# slave.net
KiCad netlist of a schematic drawn in Altium Designer
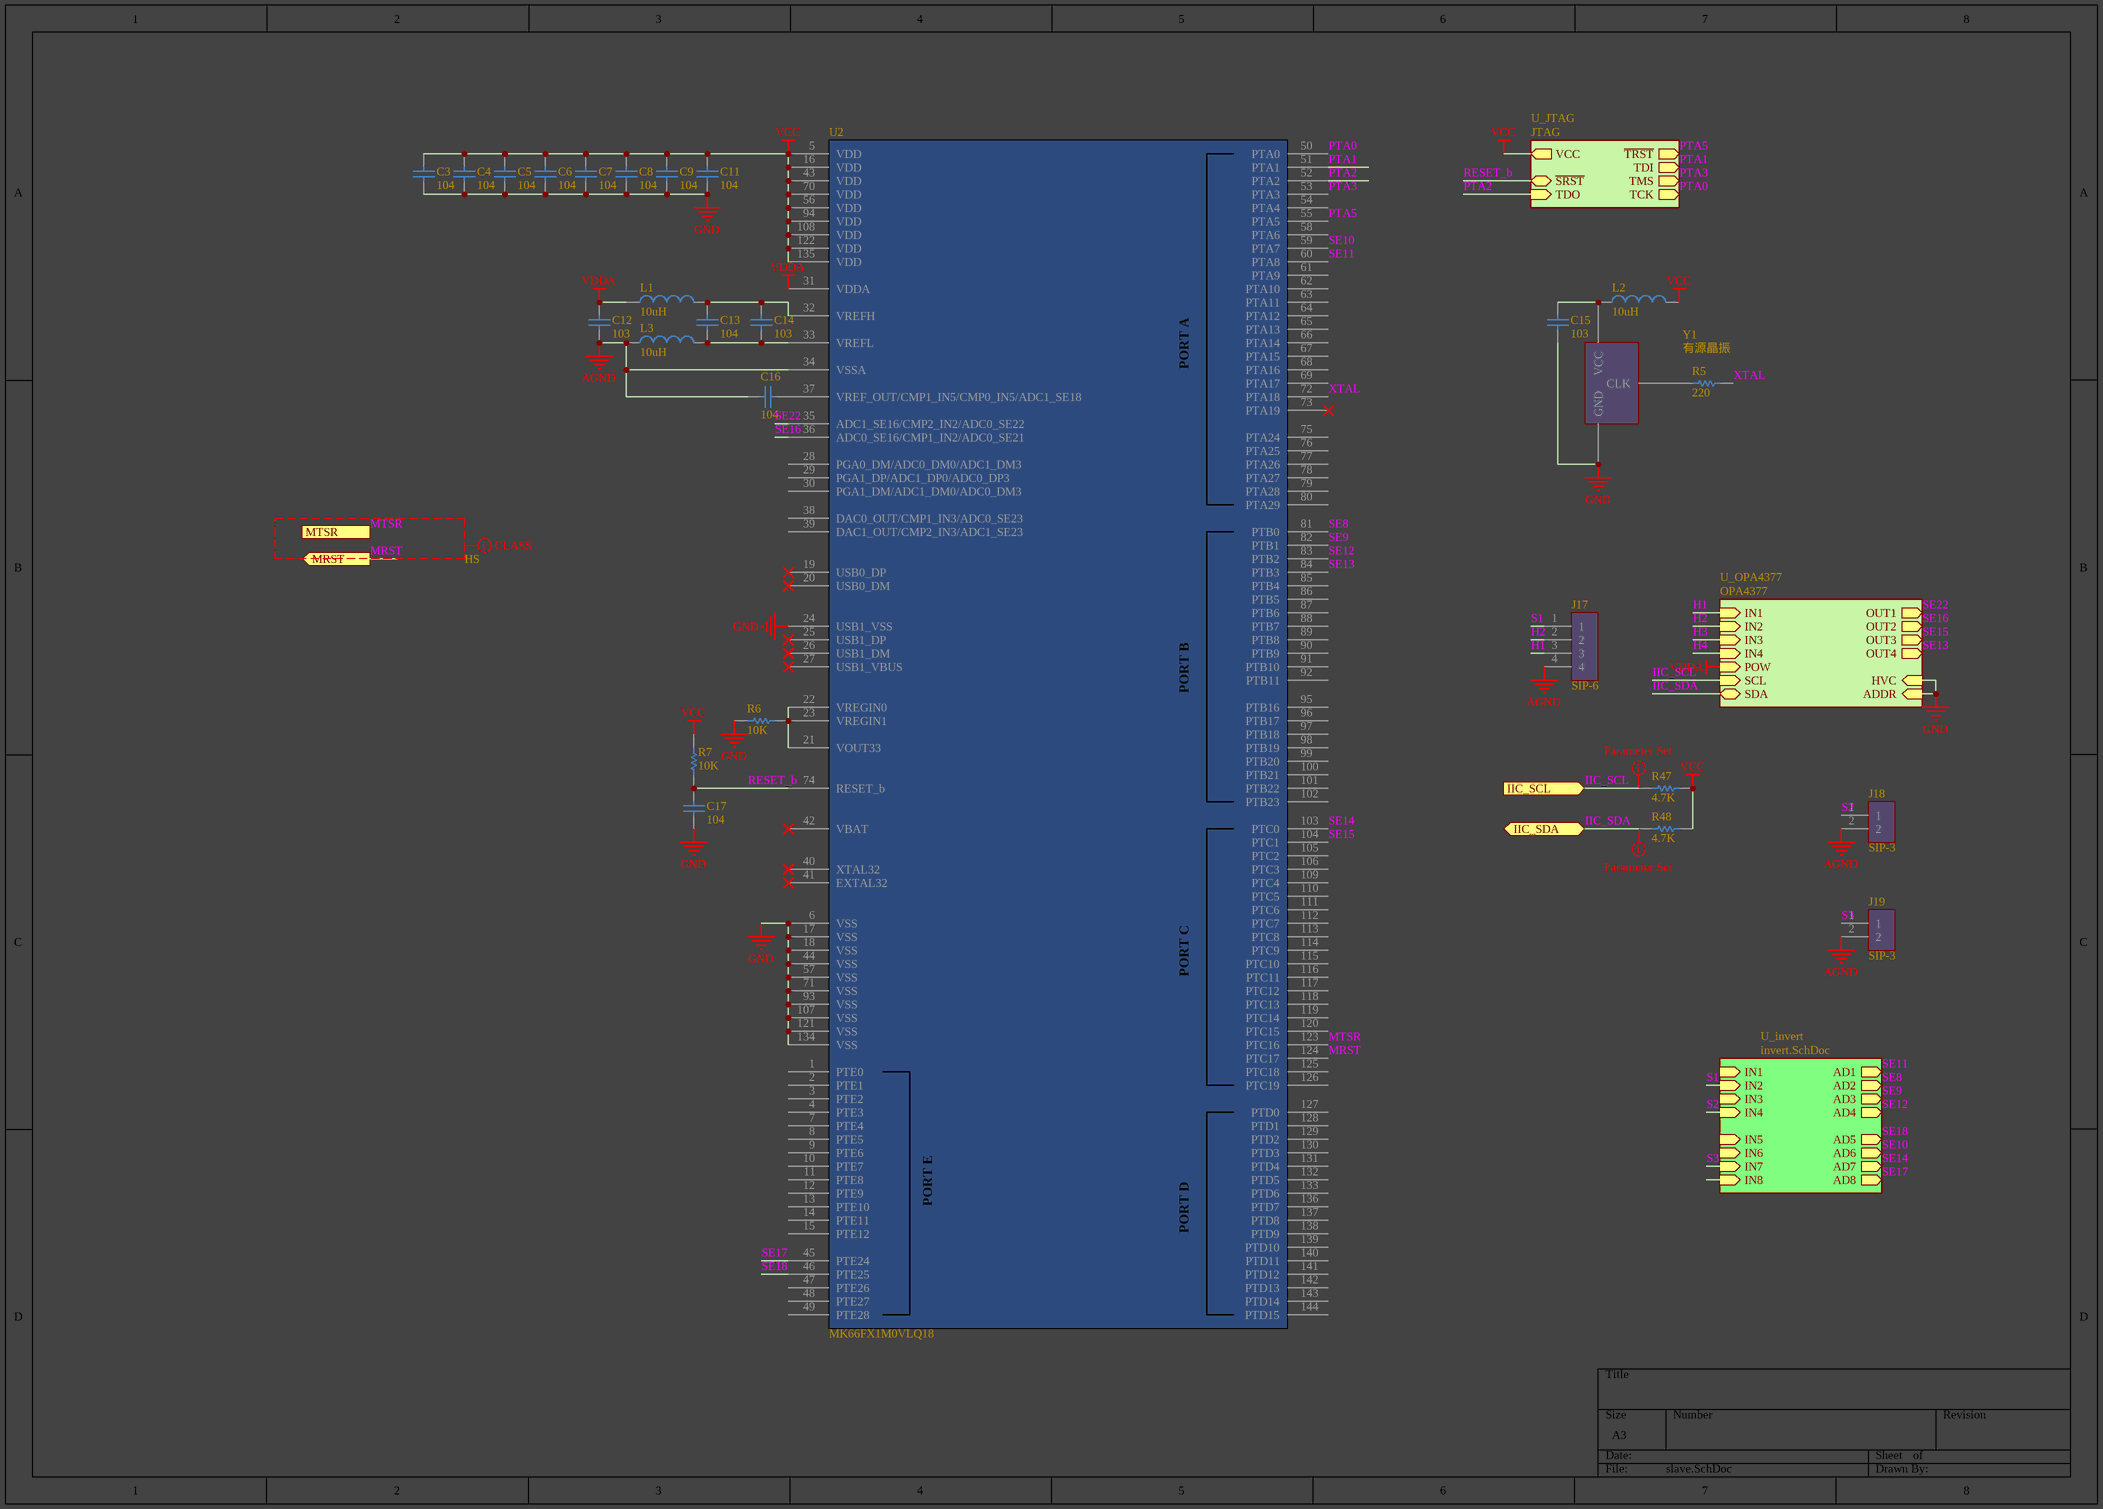
[diagram p0: slave.SchDoc]

(export (version "E")
  (design (tool "Eeschema 10.0.6"))
  (components
    (comp (ref "C3")
      (value "104")
      (footprint "C0603")
      (description "Capacitor")
      (fields (field (name "PUBLISHER") "Altium Limited"))
      (libsource (lib "iMag") (part "电容"))
    )
    (comp (ref "C4")
      (value "104")
      (footprint "C0603")
      (description "Capacitor")
      (fields (field (name "PUBLISHER") "Altium Limited"))
      (libsource (lib "iMag") (part "电容"))
    )
    (comp (ref "C5")
      (value "104")
      (footprint "C0603")
      (description "Capacitor")
      (fields (field (name "PUBLISHER") "Altium Limited"))
      (libsource (lib "iMag") (part "电容"))
    )
    (comp (ref "C6")
      (value "104")
      (footprint "C0603")
      (description "Capacitor")
      (fields (field (name "PUBLISHER") "Altium Limited"))
      (libsource (lib "iMag") (part "电容"))
    )
    (comp (ref "C7")
      (value "104")
      (footprint "C0603")
      (description "Capacitor")
      (fields (field (name "PUBLISHER") "Altium Limited"))
      (libsource (lib "iMag") (part "电容"))
    )
    (comp (ref "C8")
      (value "104")
      (footprint "C0603")
      (description "Capacitor")
      (fields (field (name "PUBLISHER") "Altium Limited"))
      (libsource (lib "iMag") (part "电容"))
    )
    (comp (ref "C9")
      (value "104")
      (footprint "C0603")
      (description "Capacitor")
      (fields (field (name "PUBLISHER") "Altium Limited"))
      (libsource (lib "iMag") (part "电容"))
    )
    (comp (ref "C11")
      (value "104")
      (footprint "C0603")
      (description "Capacitor")
      (fields (field (name "PUBLISHER") "Altium Limited"))
      (libsource (lib "iMag") (part "电容"))
    )
    (comp (ref "C12")
      (value "103")
      (footprint "C0603")
      (description "Capacitor")
      (fields (field (name "PUBLISHER") "Altium Limited"))
      (libsource (lib "iMag") (part "电容"))
    )
    (comp (ref "C13")
      (value "104")
      (footprint "C0603")
      (description "Capacitor")
      (fields (field (name "PUBLISHER") "Altium Limited"))
      (libsource (lib "iMag") (part "电容"))
    )
    (comp (ref "C14")
      (value "103")
      (footprint "C0603")
      (description "Capacitor")
      (fields (field (name "PUBLISHER") "Altium Limited"))
      (libsource (lib "iMag") (part "电容"))
    )
    (comp (ref "C15")
      (value "103")
      (footprint "C0603")
      (description "Capacitor")
      (fields (field (name "PUBLISHER") "Altium Limited"))
      (libsource (lib "iMag") (part "电容"))
    )
    (comp (ref "C16")
      (value "104")
      (footprint "C0402")
      (description "Capacitor")
      (fields (field (name "PUBLISHER") "Altium Limited"))
      (libsource (lib "iMag") (part "电容"))
    )
    (comp (ref "C17")
      (value "104")
      (footprint "C0603")
      (description "Capacitor")
      (fields (field (name "PUBLISHER") "Altium Limited"))
      (libsource (lib "iMag") (part "电容"))
    )
    (comp (ref "J17") (value "SIP-6") (footprint "2.0排针4P") (libsource (lib "iMag") (part "SIP-4")))
    (comp (ref "J18") (value "SIP-3") (footprint "GH1.25-2P") (libsource (lib "iMag") (part "SIP-2")))
    (comp (ref "J19") (value "SIP-3") (footprint "GH1.25-2P") (libsource (lib "iMag") (part "SIP-2")))
    (comp (ref "L1") (value "10uH") (footprint "L0603") (libsource (lib "iMag") (part "电感")))
    (comp (ref "L2") (value "10uH") (footprint "L0603") (libsource (lib "iMag") (part "电感")))
    (comp (ref "L3") (value "10uH") (footprint "L0603") (libsource (lib "iMag") (part "电感")))
    (comp (ref "R5")
      (value "220")
      (footprint "R0402")
      (description "Resistor")
      (fields (field (name "PUBLISHER") "Altium Limited"))
      (libsource (lib "iMag") (part "电阻"))
    )
    (comp (ref "R6")
      (value "10K")
      (footprint "R0603")
      (description "Resistor")
      (fields (field (name "PUBLISHER") "Altium Limited"))
      (libsource (lib "iMag") (part "电阻"))
    )
    (comp (ref "R7")
      (value "10K")
      (footprint "R0603")
      (description "Resistor")
      (fields (field (name "PUBLISHER") "Altium Limited"))
      (libsource (lib "iMag") (part "电阻"))
    )
    (comp (ref "R47")
      (value "4.7K")
      (footprint "R0603")
      (description "Resistor")
      (fields (field (name "PUBLISHER") "Altium Limited"))
      (libsource (lib "iMag") (part "电阻"))
    )
    (comp (ref "R48")
      (value "4.7K")
      (footprint "R0603")
      (description "Resistor")
      (fields (field (name "PUBLISHER") "Altium Limited"))
      (libsource (lib "iMag") (part "电阻"))
    )
    (comp (ref "U2")
      (value "MK66FX1M0VLQ18")
      (footprint "LQFP144 20X20")
      (libsource (lib "iMag") (part "MK66"))
    )
    (comp (ref "Y1") (value "有源晶振") (footprint "OSC 5032-4P") (libsource (lib "iMag") (part "有源晶振")))
  )
  (nets
    (net (code "1") (name "/H1") (class "Default")
      (node (ref "J17") (pin "3") (pinfunction "3_3") (pintype "passive"))
    )
    (net (code "2") (name "/H2") (class "Default")
      (node (ref "J17") (pin "2") (pinfunction "2_2") (pintype "passive"))
    )
    (net (code "5") (name "/IIC_SCL") (class "Default")
      (node (ref "R47") (pin "2") (pinfunction "2_2") (pintype "passive"))
    )
    (net (code "6") (name "/IIC_SDA") (class "Default")
      (node (ref "R48") (pin "2") (pinfunction "2_2") (pintype "passive"))
    )
    (net (code "12") (name "/MRST") (class "Default")
      (node (ref "U2") (pin "124") (pinfunction "PTC17_124") (pintype "passive"))
    )
    (net (code "13") (name "/MTSR") (class "Default")
      (node (ref "U2") (pin "123") (pinfunction "PTC16_123") (pintype "passive"))
    )
    (net (code "14") (name "/PTA0") (class "Default")
      (node (ref "U2") (pin "50") (pinfunction "PTA0_50") (pintype "passive"))
    )
    (net (code "15") (name "/PTA1") (class "Default")
      (node (ref "U2") (pin "51") (pinfunction "PTA1_51") (pintype "passive"))
    )
    (net (code "16") (name "/PTA2") (class "Default")
      (node (ref "U2") (pin "52") (pinfunction "PTA2_52") (pintype "passive"))
    )
    (net (code "17") (name "/PTA3") (class "Default")
      (node (ref "U2") (pin "53") (pinfunction "PTA3_53") (pintype "passive"))
    )
    (net (code "18") (name "/PTA5") (class "Default")
      (node (ref "U2") (pin "55") (pinfunction "PTA5_55") (pintype "passive"))
    )
    (net (code "19") (name "/RESET_b") (class "Default")
      (node (ref "C17") (pin "2") (pinfunction "2_2") (pintype "passive"))
      (node (ref "R7") (pin "1") (pinfunction "1_1") (pintype "passive"))
      (node (ref "U2") (pin "74") (pinfunction "RESET_b_74") (pintype "passive"))
    )
    (net (code "20") (name "/S1") (class "Default")
      (node (ref "J17") (pin "1") (pinfunction "1_1") (pintype "passive"))
    )
    (net (code "21") (name "/S2") (class "Default")
      (node (ref "J18") (pin "1") (pinfunction "1_1") (pintype "passive"))
    )
    (net (code "22") (name "/S3") (class "Default")
      (node (ref "J19") (pin "1") (pinfunction "1_1") (pintype "passive"))
    )
    (net (code "23") (name "/SE8") (class "Default")
      (node (ref "U2") (pin "81") (pinfunction "PTB0_81") (pintype "passive"))
    )
    (net (code "24") (name "/SE9") (class "Default")
      (node (ref "U2") (pin "82") (pinfunction "PTB1_82") (pintype "passive"))
    )
    (net (code "25") (name "/SE10") (class "Default")
      (node (ref "U2") (pin "59") (pinfunction "PTA7_59") (pintype "passive"))
    )
    (net (code "26") (name "/SE11") (class "Default")
      (node (ref "U2") (pin "60") (pinfunction "PTA8_60") (pintype "passive"))
    )
    (net (code "27") (name "/SE12") (class "Default")
      (node (ref "U2") (pin "83") (pinfunction "PTB2_83") (pintype "passive"))
    )
    (net (code "28") (name "/SE13") (class "Default")
      (node (ref "U2") (pin "84") (pinfunction "PTB3_84") (pintype "passive"))
    )
    (net (code "29") (name "/SE14") (class "Default")
      (node (ref "U2") (pin "103") (pinfunction "PTC0_103") (pintype "passive"))
    )
    (net (code "30") (name "/SE15") (class "Default")
      (node (ref "U2") (pin "104") (pinfunction "PTC1_104") (pintype "passive"))
    )
    (net (code "31") (name "/SE16") (class "Default")
      (node (ref "U2") (pin "36") (pinfunction "ADC0_SE16/CMP1_IN2/ADC0_SE21_36") (pintype "passive"))
    )
    (net (code "32") (name "/SE17") (class "Default")
      (node (ref "U2") (pin "45") (pinfunction "PTE24_45") (pintype "passive"))
    )
    (net (code "33") (name "/SE18") (class "Default")
      (node (ref "U2") (pin "46") (pinfunction "PTE25_46") (pintype "passive"))
    )
    (net (code "34") (name "/SE22") (class "Default")
      (node (ref "U2") (pin "35") (pinfunction "ADC1_SE16/CMP2_IN2/ADC0_SE22_35") (pintype "passive"))
    )
    (net (code "35") (name "/XTAL") (class "Default")
      (node (ref "R5") (pin "1") (pinfunction "1_1") (pintype "passive"))
      (node (ref "U2") (pin "72") (pinfunction "PTA18_72") (pintype "passive"))
    )
    (net (code "36") (name "AGND") (class "Default")
      (node (ref "C12") (pin "1") (pinfunction "1_1") (pintype "passive"))
      (node (ref "C16") (pin "1") (pinfunction "1_1") (pintype "passive"))
      (node (ref "J17") (pin "4") (pinfunction "4_4") (pintype "passive"))
      (node (ref "J18") (pin "2") (pinfunction "2_2") (pintype "passive"))
      (node (ref "J19") (pin "2") (pinfunction "2_2") (pintype "passive"))
      (node (ref "L3") (pin "1") (pinfunction "1_1") (pintype "passive"))
      (node (ref "U2") (pin "34") (pinfunction "VSSA_34") (pintype "passive"))
    )
    (net (code "37") (name "GND") (class "Default")
      (node (ref "C11") (pin "1") (pinfunction "1_1") (pintype "passive"))
      (node (ref "C15") (pin "1") (pinfunction "1_1") (pintype "passive"))
      (node (ref "C17") (pin "1") (pinfunction "1_1") (pintype "passive"))
      (node (ref "C3") (pin "1") (pinfunction "1_1") (pintype "passive"))
      (node (ref "C4") (pin "1") (pinfunction "1_1") (pintype "passive"))
      (node (ref "C5") (pin "1") (pinfunction "1_1") (pintype "passive"))
      (node (ref "C6") (pin "1") (pinfunction "1_1") (pintype "passive"))
      (node (ref "C7") (pin "1") (pinfunction "1_1") (pintype "passive"))
      (node (ref "C8") (pin "1") (pinfunction "1_1") (pintype "passive"))
      (node (ref "C9") (pin "1") (pinfunction "1_1") (pintype "passive"))
      (node (ref "R6") (pin "2") (pinfunction "2_2") (pintype "passive"))
      (node (ref "U2") (pin "107") (pinfunction "VSS_107") (pintype "passive"))
      (node (ref "U2") (pin "121") (pinfunction "VSS_121") (pintype "passive"))
      (node (ref "U2") (pin "134") (pinfunction "VSS_134") (pintype "passive"))
      (node (ref "U2") (pin "17") (pinfunction "VSS_17") (pintype "passive"))
      (node (ref "U2") (pin "18") (pinfunction "VSS_18") (pintype "passive"))
      (node (ref "U2") (pin "24") (pinfunction "USB1_VSS_24") (pintype "passive"))
      (node (ref "U2") (pin "44") (pinfunction "VSS_44") (pintype "passive"))
      (node (ref "U2") (pin "57") (pinfunction "VSS_57") (pintype "passive"))
      (node (ref "U2") (pin "6") (pinfunction "VSS_6") (pintype "passive"))
      (node (ref "U2") (pin "71") (pinfunction "VSS_71") (pintype "passive"))
      (node (ref "U2") (pin "93") (pinfunction "VSS_93") (pintype "passive"))
      (node (ref "Y1") (pin "2") (pinfunction "GND_2") (pintype "passive"))
    )
    (net (code "38") (name "Net-(U2-VOUT33)") (class "Default")
      (node (ref "R6") (pin "1") (pinfunction "1_1") (pintype "passive"))
      (node (ref "U2") (pin "21") (pinfunction "VOUT33_21") (pintype "passive"))
      (node (ref "U2") (pin "22") (pinfunction "VREGIN0_22") (pintype "passive"))
      (node (ref "U2") (pin "23") (pinfunction "VREGIN1_23") (pintype "passive"))
    )
    (net (code "39") (name "Net-(U2-VREFH)") (class "Default")
      (node (ref "C13") (pin "2") (pinfunction "2_2") (pintype "passive"))
      (node (ref "C14") (pin "2") (pinfunction "2_2") (pintype "passive"))
      (node (ref "L1") (pin "2") (pinfunction "2_2") (pintype "passive"))
      (node (ref "U2") (pin "32") (pinfunction "VREFH_32") (pintype "passive"))
    )
    (net (code "40") (name "Net-(U2-VREFL)") (class "Default")
      (node (ref "C13") (pin "1") (pinfunction "1_1") (pintype "passive"))
      (node (ref "C14") (pin "1") (pinfunction "1_1") (pintype "passive"))
      (node (ref "L3") (pin "2") (pinfunction "2_2") (pintype "passive"))
      (node (ref "U2") (pin "33") (pinfunction "VREFL_33") (pintype "passive"))
    )
    (net (code "41") (name "Net-(U2-VREF_OUT{slash}CMP1_IN5{slash}CMP0_IN5{slash}ADC1_SE18)") (class "Default")
      (node (ref "C16") (pin "2") (pinfunction "2_2") (pintype "passive"))
      (node (ref "U2") (pin "37") (pinfunction "VREF_OUT/CMP1_IN5/CMP0_IN5/ADC1_SE18_37") (pintype "passive"))
    )
    (net (code "42") (name "Net-(Y1-CLK)") (class "Default")
      (node (ref "R5") (pin "2") (pinfunction "2_2") (pintype "passive"))
      (node (ref "Y1") (pin "3") (pinfunction "CLK_3") (pintype "passive"))
    )
    (net (code "43") (name "Net-(Y1-VCC)") (class "Default")
      (node (ref "C15") (pin "2") (pinfunction "2_2") (pintype "passive"))
      (node (ref "L2") (pin "1") (pinfunction "1_1") (pintype "passive"))
      (node (ref "Y1") (pin "4") (pinfunction "VCC_4") (pintype "passive"))
    )
    (net (code "44") (name "VCC") (class "Default")
      (node (ref "C11") (pin "2") (pinfunction "2_2") (pintype "passive"))
      (node (ref "C3") (pin "2") (pinfunction "2_2") (pintype "passive"))
      (node (ref "C4") (pin "2") (pinfunction "2_2") (pintype "passive"))
      (node (ref "C5") (pin "2") (pinfunction "2_2") (pintype "passive"))
      (node (ref "C6") (pin "2") (pinfunction "2_2") (pintype "passive"))
      (node (ref "C7") (pin "2") (pinfunction "2_2") (pintype "passive"))
      (node (ref "C8") (pin "2") (pinfunction "2_2") (pintype "passive"))
      (node (ref "C9") (pin "2") (pinfunction "2_2") (pintype "passive"))
      (node (ref "L2") (pin "2") (pinfunction "2_2") (pintype "passive"))
      (node (ref "R47") (pin "1") (pinfunction "1_1") (pintype "passive"))
      (node (ref "R48") (pin "1") (pinfunction "1_1") (pintype "passive"))
      (node (ref "R7") (pin "2") (pinfunction "2_2") (pintype "passive"))
      (node (ref "U2") (pin "108") (pinfunction "VDD_108") (pintype "passive"))
      (node (ref "U2") (pin "122") (pinfunction "VDD_122") (pintype "passive"))
      (node (ref "U2") (pin "135") (pinfunction "VDD_135") (pintype "passive"))
      (node (ref "U2") (pin "16") (pinfunction "VDD_16") (pintype "passive"))
      (node (ref "U2") (pin "43") (pinfunction "VDD_43") (pintype "passive"))
      (node (ref "U2") (pin "5") (pinfunction "VDD_5") (pintype "passive"))
      (node (ref "U2") (pin "56") (pinfunction "VDD_56") (pintype "passive"))
      (node (ref "U2") (pin "70") (pinfunction "VDD_70") (pintype "passive"))
      (node (ref "U2") (pin "94") (pinfunction "VDD_94") (pintype "passive"))
    )
    (net (code "45") (name "VDDA") (class "Default")
      (node (ref "C12") (pin "2") (pinfunction "2_2") (pintype "passive"))
      (node (ref "L1") (pin "1") (pinfunction "1_1") (pintype "passive"))
      (node (ref "U2") (pin "31") (pinfunction "VDDA_31") (pintype "passive"))
    )
    (net (code "46") (name "unconnected-(U2-DAC0_OUT{slash}CMP1_IN3{slash}ADC0_SE23-Pad38)") (class "Default")
      (node (ref "U2") (pin "38") (pinfunction "DAC0_OUT/CMP1_IN3/ADC0_SE23_38") (pintype "passive"))
    )
    (net (code "47") (name "unconnected-(U2-DAC1_OUT{slash}CMP2_IN3{slash}ADC1_SE23-Pad39)") (class "Default")
      (node (ref "U2") (pin "39") (pinfunction "DAC1_OUT/CMP2_IN3/ADC1_SE23_39") (pintype "passive"))
    )
    (net (code "48") (name "unconnected-(U2-EXTAL32-Pad41)") (class "Default")
      (node (ref "U2") (pin "41") (pinfunction "EXTAL32_41") (pintype "passive+no_connect"))
    )
    (net (code "49") (name "unconnected-(U2-PGA0_DM{slash}ADC0_DM0{slash}ADC1_DM3-Pad28)") (class "Default")
      (node (ref "U2") (pin "28") (pinfunction "PGA0_DM/ADC0_DM0/ADC1_DM3_28") (pintype "passive"))
    )
    (net (code "50") (name "unconnected-(U2-PGA1_DM{slash}ADC1_DM0{slash}ADC0_DM3-Pad30)") (class "Default")
      (node (ref "U2") (pin "30") (pinfunction "PGA1_DM/ADC1_DM0/ADC0_DM3_30") (pintype "passive"))
    )
    (net (code "51") (name "unconnected-(U2-PGA1_DP{slash}ADC1_DP0{slash}ADC0_DP3-Pad29)") (class "Default")
      (node (ref "U2") (pin "29") (pinfunction "PGA1_DP/ADC1_DP0/ADC0_DP3_29") (pintype "passive"))
    )
    (net (code "52") (name "unconnected-(U2-PTA4-Pad54)") (class "Default")
      (node (ref "U2") (pin "54") (pinfunction "PTA4_54") (pintype "passive"))
    )
    (net (code "53") (name "unconnected-(U2-PTA6-Pad58)") (class "Default")
      (node (ref "U2") (pin "58") (pinfunction "PTA6_58") (pintype "passive"))
    )
    (net (code "54") (name "unconnected-(U2-PTA9-Pad61)") (class "Default")
      (node (ref "U2") (pin "61") (pinfunction "PTA9_61") (pintype "passive"))
    )
    (net (code "55") (name "unconnected-(U2-PTA10-Pad62)") (class "Default")
      (node (ref "U2") (pin "62") (pinfunction "PTA10_62") (pintype "passive"))
    )
    (net (code "56") (name "unconnected-(U2-PTA11-Pad63)") (class "Default")
      (node (ref "U2") (pin "63") (pinfunction "PTA11_63") (pintype "passive"))
    )
    (net (code "57") (name "unconnected-(U2-PTA12-Pad64)") (class "Default")
      (node (ref "U2") (pin "64") (pinfunction "PTA12_64") (pintype "passive"))
    )
    (net (code "58") (name "unconnected-(U2-PTA13-Pad65)") (class "Default")
      (node (ref "U2") (pin "65") (pinfunction "PTA13_65") (pintype "passive"))
    )
    (net (code "59") (name "unconnected-(U2-PTA14-Pad66)") (class "Default")
      (node (ref "U2") (pin "66") (pinfunction "PTA14_66") (pintype "passive"))
    )
    (net (code "60") (name "unconnected-(U2-PTA15-Pad67)") (class "Default")
      (node (ref "U2") (pin "67") (pinfunction "PTA15_67") (pintype "passive"))
    )
    (net (code "61") (name "unconnected-(U2-PTA16-Pad68)") (class "Default")
      (node (ref "U2") (pin "68") (pinfunction "PTA16_68") (pintype "passive"))
    )
    (net (code "62") (name "unconnected-(U2-PTA17-Pad69)") (class "Default")
      (node (ref "U2") (pin "69") (pinfunction "PTA17_69") (pintype "passive"))
    )
    (net (code "63") (name "unconnected-(U2-PTA19-Pad73)") (class "Default")
      (node (ref "U2") (pin "73") (pinfunction "PTA19_73") (pintype "passive+no_connect"))
    )
    (net (code "64") (name "unconnected-(U2-PTA24-Pad75)") (class "Default")
      (node (ref "U2") (pin "75") (pinfunction "PTA24_75") (pintype "passive"))
    )
    (net (code "65") (name "unconnected-(U2-PTA25-Pad76)") (class "Default")
      (node (ref "U2") (pin "76") (pinfunction "PTA25_76") (pintype "passive"))
    )
    (net (code "66") (name "unconnected-(U2-PTA26-Pad77)") (class "Default")
      (node (ref "U2") (pin "77") (pinfunction "PTA26_77") (pintype "passive"))
    )
    (net (code "67") (name "unconnected-(U2-PTA27-Pad78)") (class "Default")
      (node (ref "U2") (pin "78") (pinfunction "PTA27_78") (pintype "passive"))
    )
    (net (code "68") (name "unconnected-(U2-PTA28-Pad79)") (class "Default")
      (node (ref "U2") (pin "79") (pinfunction "PTA28_79") (pintype "passive"))
    )
    (net (code "69") (name "unconnected-(U2-PTA29-Pad80)") (class "Default")
      (node (ref "U2") (pin "80") (pinfunction "PTA29_80") (pintype "passive"))
    )
    (net (code "70") (name "unconnected-(U2-PTB4-Pad85)") (class "Default")
      (node (ref "U2") (pin "85") (pinfunction "PTB4_85") (pintype "passive"))
    )
    (net (code "71") (name "unconnected-(U2-PTB5-Pad86)") (class "Default")
      (node (ref "U2") (pin "86") (pinfunction "PTB5_86") (pintype "passive"))
    )
    (net (code "72") (name "unconnected-(U2-PTB6-Pad87)") (class "Default")
      (node (ref "U2") (pin "87") (pinfunction "PTB6_87") (pintype "passive"))
    )
    (net (code "73") (name "unconnected-(U2-PTB7-Pad88)") (class "Default")
      (node (ref "U2") (pin "88") (pinfunction "PTB7_88") (pintype "passive"))
    )
    (net (code "74") (name "unconnected-(U2-PTB8-Pad89)") (class "Default")
      (node (ref "U2") (pin "89") (pinfunction "PTB8_89") (pintype "passive"))
    )
    (net (code "75") (name "unconnected-(U2-PTB9-Pad90)") (class "Default")
      (node (ref "U2") (pin "90") (pinfunction "PTB9_90") (pintype "passive"))
    )
    (net (code "76") (name "unconnected-(U2-PTB10-Pad91)") (class "Default")
      (node (ref "U2") (pin "91") (pinfunction "PTB10_91") (pintype "passive"))
    )
    (net (code "77") (name "unconnected-(U2-PTB11-Pad92)") (class "Default")
      (node (ref "U2") (pin "92") (pinfunction "PTB11_92") (pintype "passive"))
    )
    (net (code "78") (name "unconnected-(U2-PTB16-Pad95)") (class "Default")
      (node (ref "U2") (pin "95") (pinfunction "PTB16_95") (pintype "passive"))
    )
    (net (code "79") (name "unconnected-(U2-PTB17-Pad96)") (class "Default")
      (node (ref "U2") (pin "96") (pinfunction "PTB17_96") (pintype "passive"))
    )
    (net (code "80") (name "unconnected-(U2-PTB18-Pad97)") (class "Default")
      (node (ref "U2") (pin "97") (pinfunction "PTB18_97") (pintype "passive"))
    )
    (net (code "81") (name "unconnected-(U2-PTB19-Pad98)") (class "Default")
      (node (ref "U2") (pin "98") (pinfunction "PTB19_98") (pintype "passive"))
    )
    (net (code "82") (name "unconnected-(U2-PTB20-Pad99)") (class "Default")
      (node (ref "U2") (pin "99") (pinfunction "PTB20_99") (pintype "passive"))
    )
    (net (code "83") (name "unconnected-(U2-PTB21-Pad100)") (class "Default")
      (node (ref "U2") (pin "100") (pinfunction "PTB21_100") (pintype "passive"))
    )
    (net (code "84") (name "unconnected-(U2-PTB22-Pad101)") (class "Default")
      (node (ref "U2") (pin "101") (pinfunction "PTB22_101") (pintype "passive"))
    )
    (net (code "85") (name "unconnected-(U2-PTB23-Pad102)") (class "Default")
      (node (ref "U2") (pin "102") (pinfunction "PTB23_102") (pintype "passive"))
    )
    (net (code "86") (name "unconnected-(U2-PTC2-Pad105)") (class "Default")
      (node (ref "U2") (pin "105") (pinfunction "PTC2_105") (pintype "passive"))
    )
    (net (code "87") (name "unconnected-(U2-PTC3-Pad106)") (class "Default")
      (node (ref "U2") (pin "106") (pinfunction "PTC3_106") (pintype "passive"))
    )
    (net (code "88") (name "unconnected-(U2-PTC4-Pad109)") (class "Default")
      (node (ref "U2") (pin "109") (pinfunction "PTC4_109") (pintype "passive"))
    )
    (net (code "89") (name "unconnected-(U2-PTC5-Pad110)") (class "Default")
      (node (ref "U2") (pin "110") (pinfunction "PTC5_110") (pintype "passive"))
    )
    (net (code "90") (name "unconnected-(U2-PTC6-Pad111)") (class "Default")
      (node (ref "U2") (pin "111") (pinfunction "PTC6_111") (pintype "passive"))
    )
    (net (code "91") (name "unconnected-(U2-PTC7-Pad112)") (class "Default")
      (node (ref "U2") (pin "112") (pinfunction "PTC7_112") (pintype "passive"))
    )
    (net (code "92") (name "unconnected-(U2-PTC8-Pad113)") (class "Default")
      (node (ref "U2") (pin "113") (pinfunction "PTC8_113") (pintype "passive"))
    )
    (net (code "93") (name "unconnected-(U2-PTC9-Pad114)") (class "Default")
      (node (ref "U2") (pin "114") (pinfunction "PTC9_114") (pintype "passive"))
    )
    (net (code "94") (name "unconnected-(U2-PTC10-Pad115)") (class "Default")
      (node (ref "U2") (pin "115") (pinfunction "PTC10_115") (pintype "passive"))
    )
    (net (code "95") (name "unconnected-(U2-PTC11-Pad116)") (class "Default")
      (node (ref "U2") (pin "116") (pinfunction "PTC11_116") (pintype "passive"))
    )
    (net (code "96") (name "unconnected-(U2-PTC12-Pad117)") (class "Default")
      (node (ref "U2") (pin "117") (pinfunction "PTC12_117") (pintype "passive"))
    )
    (net (code "97") (name "unconnected-(U2-PTC13-Pad118)") (class "Default")
      (node (ref "U2") (pin "118") (pinfunction "PTC13_118") (pintype "passive"))
    )
    (net (code "98") (name "unconnected-(U2-PTC14-Pad119)") (class "Default")
      (node (ref "U2") (pin "119") (pinfunction "PTC14_119") (pintype "passive"))
    )
    (net (code "99") (name "unconnected-(U2-PTC15-Pad120)") (class "Default")
      (node (ref "U2") (pin "120") (pinfunction "PTC15_120") (pintype "passive"))
    )
    (net (code "100") (name "unconnected-(U2-PTC18-Pad125)") (class "Default")
      (node (ref "U2") (pin "125") (pinfunction "PTC18_125") (pintype "passive"))
    )
    (net (code "101") (name "unconnected-(U2-PTC19-Pad126)") (class "Default")
      (node (ref "U2") (pin "126") (pinfunction "PTC19_126") (pintype "passive"))
    )
    (net (code "102") (name "unconnected-(U2-PTD0-Pad127)") (class "Default")
      (node (ref "U2") (pin "127") (pinfunction "PTD0_127") (pintype "passive"))
    )
    (net (code "103") (name "unconnected-(U2-PTD1-Pad128)") (class "Default")
      (node (ref "U2") (pin "128") (pinfunction "PTD1_128") (pintype "passive"))
    )
    (net (code "104") (name "unconnected-(U2-PTD2-Pad129)") (class "Default")
      (node (ref "U2") (pin "129") (pinfunction "PTD2_129") (pintype "passive"))
    )
    (net (code "105") (name "unconnected-(U2-PTD3-Pad130)") (class "Default")
      (node (ref "U2") (pin "130") (pinfunction "PTD3_130") (pintype "passive"))
    )
    (net (code "106") (name "unconnected-(U2-PTD4-Pad131)") (class "Default")
      (node (ref "U2") (pin "131") (pinfunction "PTD4_131") (pintype "passive"))
    )
    (net (code "107") (name "unconnected-(U2-PTD5-Pad132)") (class "Default")
      (node (ref "U2") (pin "132") (pinfunction "PTD5_132") (pintype "passive"))
    )
    (net (code "108") (name "unconnected-(U2-PTD6-Pad133)") (class "Default")
      (node (ref "U2") (pin "133") (pinfunction "PTD6_133") (pintype "passive"))
    )
    (net (code "109") (name "unconnected-(U2-PTD7-Pad136)") (class "Default")
      (node (ref "U2") (pin "136") (pinfunction "PTD7_136") (pintype "passive"))
    )
    (net (code "110") (name "unconnected-(U2-PTD8-Pad137)") (class "Default")
      (node (ref "U2") (pin "137") (pinfunction "PTD8_137") (pintype "passive"))
    )
    (net (code "111") (name "unconnected-(U2-PTD9-Pad138)") (class "Default")
      (node (ref "U2") (pin "138") (pinfunction "PTD9_138") (pintype "passive"))
    )
    (net (code "112") (name "unconnected-(U2-PTD10-Pad139)") (class "Default")
      (node (ref "U2") (pin "139") (pinfunction "PTD10_139") (pintype "passive"))
    )
    (net (code "113") (name "unconnected-(U2-PTD11-Pad140)") (class "Default")
      (node (ref "U2") (pin "140") (pinfunction "PTD11_140") (pintype "passive"))
    )
    (net (code "114") (name "unconnected-(U2-PTD12-Pad141)") (class "Default")
      (node (ref "U2") (pin "141") (pinfunction "PTD12_141") (pintype "passive"))
    )
    (net (code "115") (name "unconnected-(U2-PTD13-Pad142)") (class "Default")
      (node (ref "U2") (pin "142") (pinfunction "PTD13_142") (pintype "passive"))
    )
    (net (code "116") (name "unconnected-(U2-PTD14-Pad143)") (class "Default")
      (node (ref "U2") (pin "143") (pinfunction "PTD14_143") (pintype "passive"))
    )
    (net (code "117") (name "unconnected-(U2-PTD15-Pad144)") (class "Default")
      (node (ref "U2") (pin "144") (pinfunction "PTD15_144") (pintype "passive"))
    )
    (net (code "118") (name "unconnected-(U2-PTE0-Pad1)") (class "Default")
      (node (ref "U2") (pin "1") (pinfunction "PTE0_1") (pintype "passive"))
    )
    (net (code "119") (name "unconnected-(U2-PTE1-Pad2)") (class "Default")
      (node (ref "U2") (pin "2") (pinfunction "PTE1_2") (pintype "passive"))
    )
    (net (code "120") (name "unconnected-(U2-PTE2-Pad3)") (class "Default")
      (node (ref "U2") (pin "3") (pinfunction "PTE2_3") (pintype "passive"))
    )
    (net (code "121") (name "unconnected-(U2-PTE3-Pad4)") (class "Default")
      (node (ref "U2") (pin "4") (pinfunction "PTE3_4") (pintype "passive"))
    )
    (net (code "122") (name "unconnected-(U2-PTE4-Pad7)") (class "Default")
      (node (ref "U2") (pin "7") (pinfunction "PTE4_7") (pintype "passive"))
    )
    (net (code "123") (name "unconnected-(U2-PTE5-Pad8)") (class "Default")
      (node (ref "U2") (pin "8") (pinfunction "PTE5_8") (pintype "passive"))
    )
    (net (code "124") (name "unconnected-(U2-PTE6-Pad9)") (class "Default")
      (node (ref "U2") (pin "9") (pinfunction "PTE6_9") (pintype "passive"))
    )
    (net (code "125") (name "unconnected-(U2-PTE7-Pad10)") (class "Default")
      (node (ref "U2") (pin "10") (pinfunction "PTE7_10") (pintype "passive"))
    )
    (net (code "126") (name "unconnected-(U2-PTE8-Pad11)") (class "Default")
      (node (ref "U2") (pin "11") (pinfunction "PTE8_11") (pintype "passive"))
    )
    (net (code "127") (name "unconnected-(U2-PTE9-Pad12)") (class "Default")
      (node (ref "U2") (pin "12") (pinfunction "PTE9_12") (pintype "passive"))
    )
    (net (code "128") (name "unconnected-(U2-PTE10-Pad13)") (class "Default")
      (node (ref "U2") (pin "13") (pinfunction "PTE10_13") (pintype "passive"))
    )
    (net (code "129") (name "unconnected-(U2-PTE11-Pad14)") (class "Default")
      (node (ref "U2") (pin "14") (pinfunction "PTE11_14") (pintype "passive"))
    )
    (net (code "130") (name "unconnected-(U2-PTE12-Pad15)") (class "Default")
      (node (ref "U2") (pin "15") (pinfunction "PTE12_15") (pintype "passive"))
    )
    (net (code "131") (name "unconnected-(U2-PTE26-Pad47)") (class "Default")
      (node (ref "U2") (pin "47") (pinfunction "PTE26_47") (pintype "passive"))
    )
    (net (code "132") (name "unconnected-(U2-PTE27-Pad48)") (class "Default")
      (node (ref "U2") (pin "48") (pinfunction "PTE27_48") (pintype "passive"))
    )
    (net (code "133") (name "unconnected-(U2-PTE28-Pad49)") (class "Default")
      (node (ref "U2") (pin "49") (pinfunction "PTE28_49") (pintype "passive"))
    )
    (net (code "134") (name "unconnected-(U2-USB0_DM-Pad20)") (class "Default")
      (node (ref "U2") (pin "20") (pinfunction "USB0_DM_20") (pintype "passive+no_connect"))
    )
    (net (code "135") (name "unconnected-(U2-USB0_DP-Pad19)") (class "Default")
      (node (ref "U2") (pin "19") (pinfunction "USB0_DP_19") (pintype "passive+no_connect"))
    )
    (net (code "136") (name "unconnected-(U2-USB1_DM-Pad26)") (class "Default")
      (node (ref "U2") (pin "26") (pinfunction "USB1_DM_26") (pintype "passive+no_connect"))
    )
    (net (code "137") (name "unconnected-(U2-USB1_DP-Pad25)") (class "Default")
      (node (ref "U2") (pin "25") (pinfunction "USB1_DP_25") (pintype "passive+no_connect"))
    )
    (net (code "138") (name "unconnected-(U2-USB1_VBUS-Pad27)") (class "Default")
      (node (ref "U2") (pin "27") (pinfunction "USB1_VBUS_27") (pintype "passive+no_connect"))
    )
    (net (code "139") (name "unconnected-(U2-VBAT-Pad42)") (class "Default")
      (node (ref "U2") (pin "42") (pinfunction "VBAT_42") (pintype "passive+no_connect"))
    )
    (net (code "140") (name "unconnected-(U2-XTAL32-Pad40)") (class "Default")
      (node (ref "U2") (pin "40") (pinfunction "XTAL32_40") (pintype "passive+no_connect"))
    )
  )
)
